# DMXW_Driver_Board.net
KiCad netlist of a schematic drawn in EAGLE
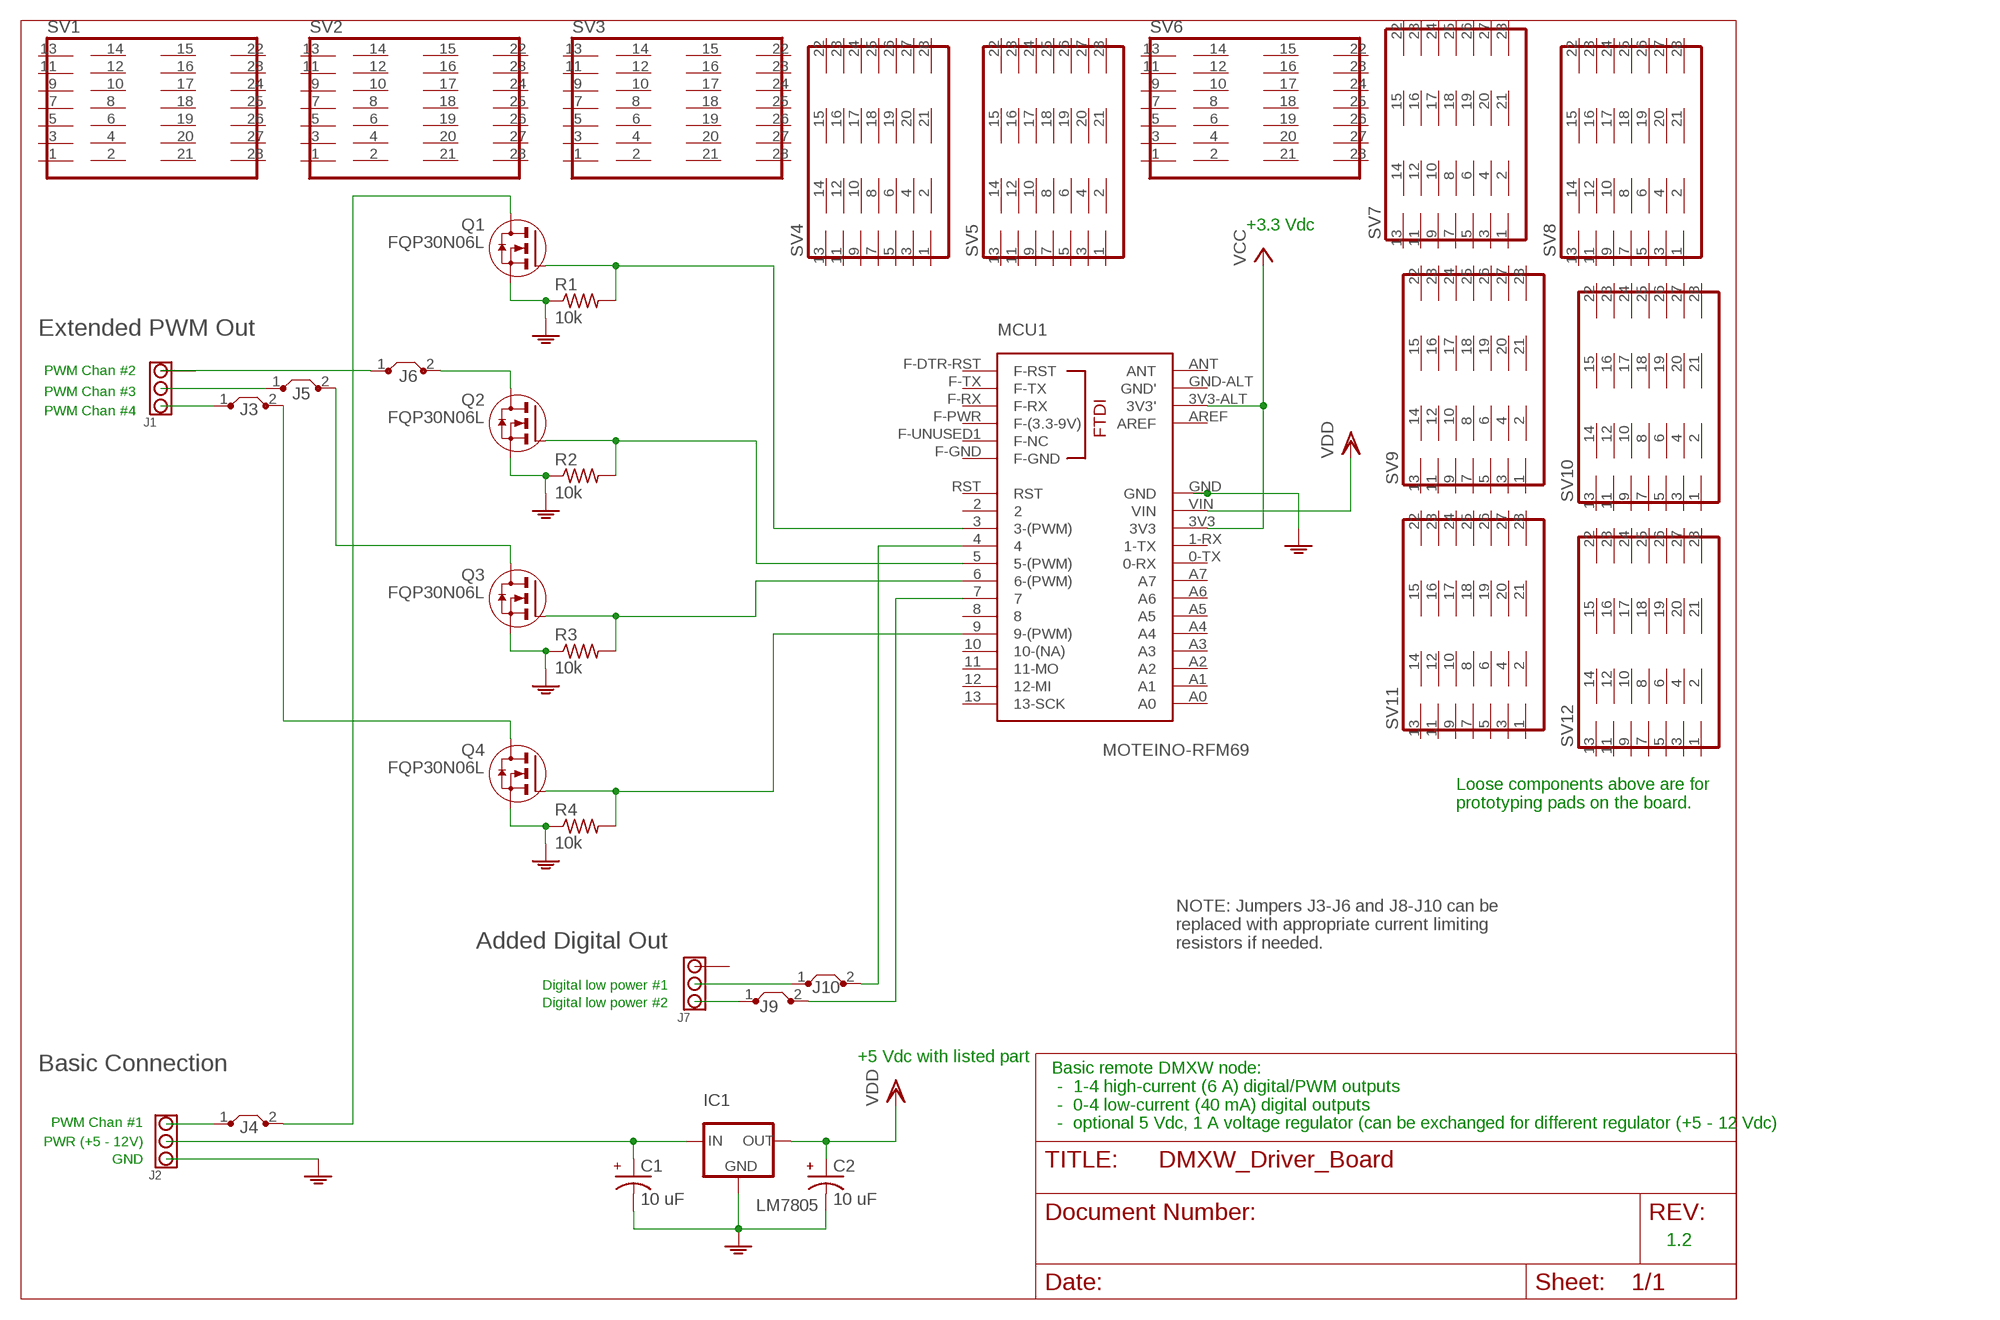
[diagram p0: schematic, sheet 1]

(export (version "E")
  (design (tool "Eeschema 10.0.6"))
  (components
    (comp (ref "C1")
      (value "10 uF")
      (footprint "eagle-import:RADIAL-CANISTER")
      (libsource (lib "eagle-import") (part "CAPACITOR-ELECTROLYTICRADIALCANISTER"))
    )
    (comp (ref "C2")
      (value "10 uF")
      (footprint "eagle-import:RADIAL-CANISTER")
      (libsource (lib "eagle-import") (part "CAPACITOR-ELECTROLYTICRADIALCANISTER"))
    )
    (comp (ref "IC1")
      (value "LM7805")
      (footprint "eagle-import:TO-220")
      (libsource (lib "eagle-import") (part "78XX-VOLTAGEREGULATORS"))
    )
    (comp (ref "J1")
      (value "TERMINAL-BLOCK-3")
      (footprint "eagle-import:W237-103")
      (libsource (lib "eagle-import") (part "TERMINAL-BLOCK-3"))
    )
    (comp (ref "J2")
      (value "TERMINAL-BLOCK-3")
      (footprint "eagle-import:W237-103")
      (libsource (lib "eagle-import") (part "TERMINAL-BLOCK-3"))
    )
    (comp (ref "J3")
      (value "J5MM")
      (footprint "eagle-import:05")
      (libsource (lib "eagle-import") (part "J5MM"))
    )
    (comp (ref "J4")
      (value "J5MM")
      (footprint "eagle-import:05")
      (libsource (lib "eagle-import") (part "J5MM"))
    )
    (comp (ref "J5")
      (value "J5MM")
      (footprint "eagle-import:05")
      (libsource (lib "eagle-import") (part "J5MM"))
    )
    (comp (ref "J6")
      (value "J5MM")
      (footprint "eagle-import:05")
      (libsource (lib "eagle-import") (part "J5MM"))
    )
    (comp (ref "J7")
      (value "TERMINAL-BLOCK-3")
      (footprint "eagle-import:W237-103")
      (libsource (lib "eagle-import") (part "TERMINAL-BLOCK-3"))
    )
    (comp (ref "J9")
      (value "J5MM")
      (footprint "eagle-import:05")
      (libsource (lib "eagle-import") (part "J5MM"))
    )
    (comp (ref "J10")
      (value "J5MM")
      (footprint "eagle-import:05")
      (libsource (lib "eagle-import") (part "J5MM"))
    )
    (comp (ref "MCU1")
      (value "MOTEINO-RFM69")
      (footprint "eagle-import:MOTEINO")
      (libsource (lib "eagle-import") (part "MOTEINO-RFM69"))
    )
    (comp (ref "Q1")
      (value "FQP30N06L")
      (footprint "eagle-import:TO-220")
      (libsource (lib "eagle-import") (part "MOSFET-N-FQP30N06L"))
    )
    (comp (ref "Q2")
      (value "FQP30N06L")
      (footprint "eagle-import:TO-220")
      (libsource (lib "eagle-import") (part "MOSFET-N-FQP30N06L"))
    )
    (comp (ref "Q3")
      (value "FQP30N06L")
      (footprint "eagle-import:TO-220")
      (libsource (lib "eagle-import") (part "MOSFET-N-FQP30N06L"))
    )
    (comp (ref "Q4")
      (value "FQP30N06L")
      (footprint "eagle-import:TO-220")
      (libsource (lib "eagle-import") (part "MOSFET-N-FQP30N06L"))
    )
    (comp (ref "R1")
      (value "10k")
      (footprint "eagle-import:0207_10")
      (libsource (lib "eagle-import") (part "R-US_0207/10"))
    )
    (comp (ref "R2")
      (value "10k")
      (footprint "eagle-import:0207_10")
      (libsource (lib "eagle-import") (part "R-US_0207/10"))
    )
    (comp (ref "R3")
      (value "10k")
      (footprint "eagle-import:0207_10")
      (libsource (lib "eagle-import") (part "R-US_0207/10"))
    )
    (comp (ref "R4")
      (value "10k")
      (footprint "eagle-import:0207_10")
      (libsource (lib "eagle-import") (part "R-US_0207/10"))
    )
    (comp (ref "SV1")
      (value "14P")
      (footprint "eagle-import:14P")
      (libsource (lib "eagle-import") (part "14P"))
    )
    (comp (ref "SV2")
      (value "14P")
      (footprint "eagle-import:14P")
      (libsource (lib "eagle-import") (part "14P"))
    )
    (comp (ref "SV3")
      (value "14P")
      (footprint "eagle-import:14P")
      (libsource (lib "eagle-import") (part "14P"))
    )
    (comp (ref "SV4")
      (value "14P")
      (footprint "eagle-import:14P")
      (libsource (lib "eagle-import") (part "14P"))
    )
    (comp (ref "SV5")
      (value "14P")
      (footprint "eagle-import:14P")
      (libsource (lib "eagle-import") (part "14P"))
    )
    (comp (ref "SV6")
      (value "14P")
      (footprint "eagle-import:14P")
      (libsource (lib "eagle-import") (part "14P"))
    )
    (comp (ref "SV7")
      (value "14P")
      (footprint "eagle-import:14P")
      (libsource (lib "eagle-import") (part "14P"))
    )
    (comp (ref "SV8")
      (value "14P")
      (footprint "eagle-import:14P")
      (libsource (lib "eagle-import") (part "14P"))
    )
    (comp (ref "SV9")
      (value "14P")
      (footprint "eagle-import:14P")
      (libsource (lib "eagle-import") (part "14P"))
    )
    (comp (ref "SV10")
      (value "14P")
      (footprint "eagle-import:14P")
      (libsource (lib "eagle-import") (part "14P"))
    )
    (comp (ref "SV11")
      (value "14P")
      (footprint "eagle-import:14P")
      (libsource (lib "eagle-import") (part "14P"))
    )
    (comp (ref "SV12")
      (value "14P")
      (footprint "eagle-import:14P")
      (libsource (lib "eagle-import") (part "14P"))
    )
  )
  (nets
    (net (code "1") (name "GND") (class "Default")
      (node (ref "C1") (pin "-") (pinfunction "-_-") (pintype "passive"))
      (node (ref "C2") (pin "-") (pinfunction "-_-") (pintype "passive"))
      (node (ref "IC1") (pin "PIN2") (pinfunction "GND_PIN2") (pintype "input"))
      (node (ref "J2") (pin "3") (pinfunction "P$3_3") (pintype "bidirectional"))
      (node (ref "MCU1") (pin "GND") (pinfunction "GND_GND") (pintype "bidirectional"))
      (node (ref "Q1") (pin "PIN3") (pinfunction "S_PIN3") (pintype "passive"))
      (node (ref "Q2") (pin "PIN3") (pinfunction "S_PIN3") (pintype "passive"))
      (node (ref "Q3") (pin "PIN3") (pinfunction "S_PIN3") (pintype "passive"))
      (node (ref "Q4") (pin "PIN3") (pinfunction "S_PIN3") (pintype "passive"))
      (node (ref "R1") (pin "1") (pinfunction "1_1") (pintype "passive"))
      (node (ref "R2") (pin "1") (pinfunction "1_1") (pintype "passive"))
      (node (ref "R3") (pin "1") (pinfunction "1_1") (pintype "passive"))
      (node (ref "R4") (pin "1") (pinfunction "1_1") (pintype "passive"))
    )
    (net (code "2") (name "Net-(IC1-IN)") (class "Default")
      (node (ref "C1") (pin "+") (pinfunction "+_+") (pintype "passive"))
      (node (ref "IC1") (pin "PIN1") (pinfunction "IN_PIN1") (pintype "input"))
      (node (ref "J2") (pin "2") (pinfunction "P$2_2") (pintype "bidirectional"))
    )
    (net (code "3") (name "Net-(J1-P$1)") (class "Default")
      (node (ref "J1") (pin "1") (pinfunction "P$1_1") (pintype "bidirectional"))
      (node (ref "J6") (pin "1") (pinfunction "1_1") (pintype "passive"))
    )
    (net (code "4") (name "Net-(J1-P$2)") (class "Default")
      (node (ref "J1") (pin "2") (pinfunction "P$2_2") (pintype "bidirectional"))
      (node (ref "J5") (pin "1") (pinfunction "1_1") (pintype "passive"))
    )
    (net (code "5") (name "Net-(J1-P$3)") (class "Default")
      (node (ref "J1") (pin "3") (pinfunction "P$3_3") (pintype "bidirectional"))
      (node (ref "J3") (pin "1") (pinfunction "1_1") (pintype "passive"))
    )
    (net (code "6") (name "Net-(J2-P$1)") (class "Default")
      (node (ref "J2") (pin "1") (pinfunction "P$1_1") (pintype "bidirectional"))
      (node (ref "J4") (pin "1") (pinfunction "1_1") (pintype "passive"))
    )
    (net (code "7") (name "Net-(J7-P$2)") (class "Default")
      (node (ref "J10") (pin "1") (pinfunction "1_1") (pintype "passive"))
      (node (ref "J7") (pin "2") (pinfunction "P$2_2") (pintype "bidirectional"))
    )
    (net (code "8") (name "Net-(J7-P$3)") (class "Default")
      (node (ref "J7") (pin "3") (pinfunction "P$3_3") (pintype "bidirectional"))
      (node (ref "J9") (pin "1") (pinfunction "1_1") (pintype "passive"))
    )
    (net (code "9") (name "Net-(J9-Pad2)") (class "Default")
      (node (ref "J9") (pin "2") (pinfunction "2_2") (pintype "passive"))
      (node (ref "MCU1") (pin "7") (pinfunction "7_7") (pintype "bidirectional"))
    )
    (net (code "10") (name "Net-(J10-Pad2)") (class "Default")
      (node (ref "J10") (pin "2") (pinfunction "2_2") (pintype "passive"))
      (node (ref "MCU1") (pin "4") (pinfunction "4_4") (pintype "bidirectional"))
    )
    (net (code "11") (name "Net-(MCU1-3-(PWM))") (class "Default")
      (node (ref "MCU1") (pin "3") (pinfunction "3-(PWM)_3") (pintype "bidirectional"))
      (node (ref "Q1") (pin "PIN1") (pinfunction "G_PIN1") (pintype "passive"))
      (node (ref "R1") (pin "2") (pinfunction "2_2") (pintype "passive"))
    )
    (net (code "12") (name "Net-(MCU1-5-(PWM))") (class "Default")
      (node (ref "MCU1") (pin "5") (pinfunction "5-(PWM)_5") (pintype "bidirectional"))
      (node (ref "Q2") (pin "PIN1") (pinfunction "G_PIN1") (pintype "passive"))
      (node (ref "R2") (pin "2") (pinfunction "2_2") (pintype "passive"))
    )
    (net (code "13") (name "Net-(MCU1-6-(PWM))") (class "Default")
      (node (ref "MCU1") (pin "6") (pinfunction "6-(PWM)_6") (pintype "bidirectional"))
      (node (ref "Q3") (pin "PIN1") (pinfunction "G_PIN1") (pintype "passive"))
      (node (ref "R3") (pin "2") (pinfunction "2_2") (pintype "passive"))
    )
    (net (code "14") (name "Net-(MCU1-9-(PWM))") (class "Default")
      (node (ref "MCU1") (pin "9") (pinfunction "9-(PWM)_9") (pintype "bidirectional"))
      (node (ref "Q4") (pin "PIN1") (pinfunction "G_PIN1") (pintype "passive"))
      (node (ref "R4") (pin "2") (pinfunction "2_2") (pintype "passive"))
    )
    (net (code "15") (name "Net-(Q1-D)") (class "Default")
      (node (ref "J4") (pin "2") (pinfunction "2_2") (pintype "passive"))
      (node (ref "Q1") (pin "PIN2") (pinfunction "D_PIN2") (pintype "passive"))
    )
    (net (code "16") (name "Net-(Q2-D)") (class "Default")
      (node (ref "J6") (pin "2") (pinfunction "2_2") (pintype "passive"))
      (node (ref "Q2") (pin "PIN2") (pinfunction "D_PIN2") (pintype "passive"))
    )
    (net (code "17") (name "Net-(Q3-D)") (class "Default")
      (node (ref "J5") (pin "2") (pinfunction "2_2") (pintype "passive"))
      (node (ref "Q3") (pin "PIN2") (pinfunction "D_PIN2") (pintype "passive"))
    )
    (net (code "18") (name "Net-(Q4-D)") (class "Default")
      (node (ref "J3") (pin "2") (pinfunction "2_2") (pintype "passive"))
      (node (ref "Q4") (pin "PIN2") (pinfunction "D_PIN2") (pintype "passive"))
    )
    (net (code "19") (name "VCC") (class "Default")
      (node (ref "MCU1") (pin "3V3") (pinfunction "3V3_3V3") (pintype "bidirectional"))
      (node (ref "MCU1") (pin "3V3-ALT") (pinfunction "3V3'_3V3-ALT") (pintype "bidirectional"))
    )
    (net (code "20") (name "VDD") (class "Default")
      (node (ref "C2") (pin "+") (pinfunction "+_+") (pintype "passive"))
      (node (ref "IC1") (pin "PIN3") (pinfunction "OUT_PIN3") (pintype "passive"))
      (node (ref "MCU1") (pin "VIN") (pinfunction "VIN_VIN") (pintype "bidirectional"))
    )
    (net (code "21") (name "unconnected-(J7-P$1-Pad1)") (class "Default")
      (node (ref "J7") (pin "1") (pinfunction "P$1_1") (pintype "bidirectional"))
    )
    (net (code "22") (name "unconnected-(MCU1-0-RX-Pad0-TX)") (class "Default")
      (node (ref "MCU1") (pin "0-TX") (pinfunction "0-RX_0-TX") (pintype "bidirectional"))
    )
    (net (code "23") (name "unconnected-(MCU1-1-TX-Pad1-RX)") (class "Default")
      (node (ref "MCU1") (pin "1-RX") (pinfunction "1-TX_1-RX") (pintype "bidirectional"))
    )
    (net (code "24") (name "unconnected-(MCU1-10-(NA)-Pad10)") (class "Default")
      (node (ref "MCU1") (pin "10") (pinfunction "10-(NA)_10") (pintype "bidirectional"))
    )
    (net (code "25") (name "unconnected-(MCU1-11-MO-Pad11)") (class "Default")
      (node (ref "MCU1") (pin "11") (pinfunction "11-MO_11") (pintype "bidirectional"))
    )
    (net (code "26") (name "unconnected-(MCU1-12-MI-Pad12)") (class "Default")
      (node (ref "MCU1") (pin "12") (pinfunction "12-MI_12") (pintype "bidirectional"))
    )
    (net (code "27") (name "unconnected-(MCU1-13-SCK-Pad13)") (class "Default")
      (node (ref "MCU1") (pin "13") (pinfunction "13-SCK_13") (pintype "bidirectional"))
    )
    (net (code "28") (name "unconnected-(MCU1-F-(3.3-9V)-PadF-PWR)") (class "Default")
      (node (ref "MCU1") (pin "F-PWR") (pinfunction "F-(3.3-9V)_F-PWR") (pintype "bidirectional"))
    )
    (net (code "29") (name "unconnected-(MCU1-F-NC-PadF-UNUSED1)") (class "Default")
      (node (ref "MCU1") (pin "F-UNUSED1") (pinfunction "F-NC_F-UNUSED1") (pintype "bidirectional"))
    )
    (net (code "30") (name "unconnected-(MCU1-F-RST-PadF-DTR-RST)") (class "Default")
      (node (ref "MCU1") (pin "F-DTR-RST") (pinfunction "F-RST_F-DTR-RST") (pintype "bidirectional"))
    )
    (net (code "31") (name "unconnected-(MCU1-GND'-PadGND-ALT)") (class "Default")
      (node (ref "MCU1") (pin "GND-ALT") (pinfunction "GND'_GND-ALT") (pintype "bidirectional"))
    )
    (net (code "32") (name "unconnected-(MCU1-Pad2)") (class "Default")
      (node (ref "MCU1") (pin "2") (pinfunction "2_2") (pintype "bidirectional"))
    )
    (net (code "33") (name "unconnected-(MCU1-Pad8)") (class "Default")
      (node (ref "MCU1") (pin "8") (pinfunction "8_8") (pintype "bidirectional"))
    )
    (net (code "34") (name "unconnected-(MCU1-PadA0)") (class "Default")
      (node (ref "MCU1") (pin "A0") (pinfunction "A0_A0") (pintype "bidirectional"))
    )
    (net (code "35") (name "unconnected-(MCU1-PadA1)") (class "Default")
      (node (ref "MCU1") (pin "A1") (pinfunction "A1_A1") (pintype "bidirectional"))
    )
    (net (code "36") (name "unconnected-(MCU1-PadA2)") (class "Default")
      (node (ref "MCU1") (pin "A2") (pinfunction "A2_A2") (pintype "bidirectional"))
    )
    (net (code "37") (name "unconnected-(MCU1-PadA3)") (class "Default")
      (node (ref "MCU1") (pin "A3") (pinfunction "A3_A3") (pintype "bidirectional"))
    )
    (net (code "38") (name "unconnected-(MCU1-PadA4)") (class "Default")
      (node (ref "MCU1") (pin "A4") (pinfunction "A4_A4") (pintype "bidirectional"))
    )
    (net (code "39") (name "unconnected-(MCU1-PadA5)") (class "Default")
      (node (ref "MCU1") (pin "A5") (pinfunction "A5_A5") (pintype "bidirectional"))
    )
    (net (code "40") (name "unconnected-(MCU1-PadA6)") (class "Default")
      (node (ref "MCU1") (pin "A6") (pinfunction "A6_A6") (pintype "bidirectional"))
    )
    (net (code "41") (name "unconnected-(MCU1-PadA7)") (class "Default")
      (node (ref "MCU1") (pin "A7") (pinfunction "A7_A7") (pintype "bidirectional"))
    )
    (net (code "42") (name "unconnected-(MCU1-PadANT)") (class "Default")
      (node (ref "MCU1") (pin "ANT") (pinfunction "ANT_ANT") (pintype "bidirectional"))
    )
    (net (code "43") (name "unconnected-(MCU1-PadAREF)") (class "Default")
      (node (ref "MCU1") (pin "AREF") (pinfunction "AREF_AREF") (pintype "bidirectional"))
    )
    (net (code "44") (name "unconnected-(MCU1-PadF-GND)") (class "Default")
      (node (ref "MCU1") (pin "F-GND") (pinfunction "F-GND_F-GND") (pintype "bidirectional"))
    )
    (net (code "45") (name "unconnected-(MCU1-PadF-RX)") (class "Default")
      (node (ref "MCU1") (pin "F-RX") (pinfunction "F-RX_F-RX") (pintype "bidirectional"))
    )
    (net (code "46") (name "unconnected-(MCU1-PadF-TX)") (class "Default")
      (node (ref "MCU1") (pin "F-TX") (pinfunction "F-TX_F-TX") (pintype "bidirectional"))
    )
    (net (code "47") (name "unconnected-(MCU1-PadRST)") (class "Default")
      (node (ref "MCU1") (pin "RST") (pinfunction "RST_RST") (pintype "bidirectional"))
    )
    (net (code "48") (name "unconnected-(SV1-Pad1)") (class "Default")
      (node (ref "SV1") (pin "1") (pinfunction "1_1") (pintype "passive"))
    )
    (net (code "49") (name "unconnected-(SV1-Pad2)") (class "Default")
      (node (ref "SV1") (pin "2") (pinfunction "2_2") (pintype "passive"))
    )
    (net (code "50") (name "unconnected-(SV1-Pad3)") (class "Default")
      (node (ref "SV1") (pin "3") (pinfunction "3_3") (pintype "passive"))
    )
    (net (code "51") (name "unconnected-(SV1-Pad4)") (class "Default")
      (node (ref "SV1") (pin "4") (pinfunction "4_4") (pintype "passive"))
    )
    (net (code "52") (name "unconnected-(SV1-Pad5)") (class "Default")
      (node (ref "SV1") (pin "5") (pinfunction "5_5") (pintype "passive"))
    )
    (net (code "53") (name "unconnected-(SV1-Pad6)") (class "Default")
      (node (ref "SV1") (pin "6") (pinfunction "6_6") (pintype "passive"))
    )
    (net (code "54") (name "unconnected-(SV1-Pad7)") (class "Default")
      (node (ref "SV1") (pin "7") (pinfunction "7_7") (pintype "passive"))
    )
    (net (code "55") (name "unconnected-(SV1-Pad8)") (class "Default")
      (node (ref "SV1") (pin "8") (pinfunction "8_8") (pintype "passive"))
    )
    (net (code "56") (name "unconnected-(SV1-Pad9)") (class "Default")
      (node (ref "SV1") (pin "9") (pinfunction "9_9") (pintype "passive"))
    )
    (net (code "57") (name "unconnected-(SV1-Pad10)") (class "Default")
      (node (ref "SV1") (pin "10") (pinfunction "10_10") (pintype "passive"))
    )
    (net (code "58") (name "unconnected-(SV1-Pad11)") (class "Default")
      (node (ref "SV1") (pin "11") (pinfunction "11_11") (pintype "passive"))
    )
    (net (code "59") (name "unconnected-(SV1-Pad12)") (class "Default")
      (node (ref "SV1") (pin "12") (pinfunction "12_12") (pintype "passive"))
    )
    (net (code "60") (name "unconnected-(SV1-Pad13)") (class "Default")
      (node (ref "SV1") (pin "13") (pinfunction "13_13") (pintype "passive"))
    )
    (net (code "61") (name "unconnected-(SV1-Pad14)") (class "Default")
      (node (ref "SV1") (pin "14") (pinfunction "14_14") (pintype "passive"))
    )
    (net (code "62") (name "unconnected-(SV1-Pad15)") (class "Default")
      (node (ref "SV1") (pin "15") (pinfunction "15_15") (pintype "passive"))
    )
    (net (code "63") (name "unconnected-(SV1-Pad16)") (class "Default")
      (node (ref "SV1") (pin "16") (pinfunction "16_16") (pintype "passive"))
    )
    (net (code "64") (name "unconnected-(SV1-Pad17)") (class "Default")
      (node (ref "SV1") (pin "17") (pinfunction "17_17") (pintype "passive"))
    )
    (net (code "65") (name "unconnected-(SV1-Pad18)") (class "Default")
      (node (ref "SV1") (pin "18") (pinfunction "18_18") (pintype "passive"))
    )
    (net (code "66") (name "unconnected-(SV1-Pad19)") (class "Default")
      (node (ref "SV1") (pin "19") (pinfunction "19_19") (pintype "passive"))
    )
    (net (code "67") (name "unconnected-(SV1-Pad20)") (class "Default")
      (node (ref "SV1") (pin "20") (pinfunction "20_20") (pintype "passive"))
    )
    (net (code "68") (name "unconnected-(SV1-Pad21)") (class "Default")
      (node (ref "SV1") (pin "21") (pinfunction "21_21") (pintype "passive"))
    )
    (net (code "69") (name "unconnected-(SV1-Pad22)") (class "Default")
      (node (ref "SV1") (pin "22") (pinfunction "22_22") (pintype "passive"))
    )
    (net (code "70") (name "unconnected-(SV1-Pad23)") (class "Default")
      (node (ref "SV1") (pin "23") (pinfunction "23_23") (pintype "passive"))
    )
    (net (code "71") (name "unconnected-(SV1-Pad24)") (class "Default")
      (node (ref "SV1") (pin "24") (pinfunction "24_24") (pintype "passive"))
    )
    (net (code "72") (name "unconnected-(SV1-Pad25)") (class "Default")
      (node (ref "SV1") (pin "25") (pinfunction "25_25") (pintype "passive"))
    )
    (net (code "73") (name "unconnected-(SV1-Pad26)") (class "Default")
      (node (ref "SV1") (pin "26") (pinfunction "26_26") (pintype "passive"))
    )
    (net (code "74") (name "unconnected-(SV1-Pad27)") (class "Default")
      (node (ref "SV1") (pin "27") (pinfunction "27_27") (pintype "passive"))
    )
    (net (code "75") (name "unconnected-(SV1-Pad28)") (class "Default")
      (node (ref "SV1") (pin "28") (pinfunction "28_28") (pintype "passive"))
    )
    (net (code "76") (name "unconnected-(SV2-Pad1)") (class "Default")
      (node (ref "SV2") (pin "1") (pinfunction "1_1") (pintype "passive"))
    )
    (net (code "77") (name "unconnected-(SV2-Pad2)") (class "Default")
      (node (ref "SV2") (pin "2") (pinfunction "2_2") (pintype "passive"))
    )
    (net (code "78") (name "unconnected-(SV2-Pad3)") (class "Default")
      (node (ref "SV2") (pin "3") (pinfunction "3_3") (pintype "passive"))
    )
    (net (code "79") (name "unconnected-(SV2-Pad4)") (class "Default")
      (node (ref "SV2") (pin "4") (pinfunction "4_4") (pintype "passive"))
    )
    (net (code "80") (name "unconnected-(SV2-Pad5)") (class "Default")
      (node (ref "SV2") (pin "5") (pinfunction "5_5") (pintype "passive"))
    )
    (net (code "81") (name "unconnected-(SV2-Pad6)") (class "Default")
      (node (ref "SV2") (pin "6") (pinfunction "6_6") (pintype "passive"))
    )
    (net (code "82") (name "unconnected-(SV2-Pad7)") (class "Default")
      (node (ref "SV2") (pin "7") (pinfunction "7_7") (pintype "passive"))
    )
    (net (code "83") (name "unconnected-(SV2-Pad8)") (class "Default")
      (node (ref "SV2") (pin "8") (pinfunction "8_8") (pintype "passive"))
    )
    (net (code "84") (name "unconnected-(SV2-Pad9)") (class "Default")
      (node (ref "SV2") (pin "9") (pinfunction "9_9") (pintype "passive"))
    )
    (net (code "85") (name "unconnected-(SV2-Pad10)") (class "Default")
      (node (ref "SV2") (pin "10") (pinfunction "10_10") (pintype "passive"))
    )
    (net (code "86") (name "unconnected-(SV2-Pad11)") (class "Default")
      (node (ref "SV2") (pin "11") (pinfunction "11_11") (pintype "passive"))
    )
    (net (code "87") (name "unconnected-(SV2-Pad12)") (class "Default")
      (node (ref "SV2") (pin "12") (pinfunction "12_12") (pintype "passive"))
    )
    (net (code "88") (name "unconnected-(SV2-Pad13)") (class "Default")
      (node (ref "SV2") (pin "13") (pinfunction "13_13") (pintype "passive"))
    )
    (net (code "89") (name "unconnected-(SV2-Pad14)") (class "Default")
      (node (ref "SV2") (pin "14") (pinfunction "14_14") (pintype "passive"))
    )
    (net (code "90") (name "unconnected-(SV2-Pad15)") (class "Default")
      (node (ref "SV2") (pin "15") (pinfunction "15_15") (pintype "passive"))
    )
    (net (code "91") (name "unconnected-(SV2-Pad16)") (class "Default")
      (node (ref "SV2") (pin "16") (pinfunction "16_16") (pintype "passive"))
    )
    (net (code "92") (name "unconnected-(SV2-Pad17)") (class "Default")
      (node (ref "SV2") (pin "17") (pinfunction "17_17") (pintype "passive"))
    )
    (net (code "93") (name "unconnected-(SV2-Pad18)") (class "Default")
      (node (ref "SV2") (pin "18") (pinfunction "18_18") (pintype "passive"))
    )
    (net (code "94") (name "unconnected-(SV2-Pad19)") (class "Default")
      (node (ref "SV2") (pin "19") (pinfunction "19_19") (pintype "passive"))
    )
    (net (code "95") (name "unconnected-(SV2-Pad20)") (class "Default")
      (node (ref "SV2") (pin "20") (pinfunction "20_20") (pintype "passive"))
    )
    (net (code "96") (name "unconnected-(SV2-Pad21)") (class "Default")
      (node (ref "SV2") (pin "21") (pinfunction "21_21") (pintype "passive"))
    )
    (net (code "97") (name "unconnected-(SV2-Pad22)") (class "Default")
      (node (ref "SV2") (pin "22") (pinfunction "22_22") (pintype "passive"))
    )
    (net (code "98") (name "unconnected-(SV2-Pad23)") (class "Default")
      (node (ref "SV2") (pin "23") (pinfunction "23_23") (pintype "passive"))
    )
    (net (code "99") (name "unconnected-(SV2-Pad24)") (class "Default")
      (node (ref "SV2") (pin "24") (pinfunction "24_24") (pintype "passive"))
    )
    (net (code "100") (name "unconnected-(SV2-Pad25)") (class "Default")
      (node (ref "SV2") (pin "25") (pinfunction "25_25") (pintype "passive"))
    )
    (net (code "101") (name "unconnected-(SV2-Pad26)") (class "Default")
      (node (ref "SV2") (pin "26") (pinfunction "26_26") (pintype "passive"))
    )
    (net (code "102") (name "unconnected-(SV2-Pad27)") (class "Default")
      (node (ref "SV2") (pin "27") (pinfunction "27_27") (pintype "passive"))
    )
    (net (code "103") (name "unconnected-(SV2-Pad28)") (class "Default")
      (node (ref "SV2") (pin "28") (pinfunction "28_28") (pintype "passive"))
    )
    (net (code "104") (name "unconnected-(SV3-Pad1)") (class "Default")
      (node (ref "SV3") (pin "1") (pinfunction "1_1") (pintype "passive"))
    )
    (net (code "105") (name "unconnected-(SV3-Pad2)") (class "Default")
      (node (ref "SV3") (pin "2") (pinfunction "2_2") (pintype "passive"))
    )
    (net (code "106") (name "unconnected-(SV3-Pad3)") (class "Default")
      (node (ref "SV3") (pin "3") (pinfunction "3_3") (pintype "passive"))
    )
    (net (code "107") (name "unconnected-(SV3-Pad4)") (class "Default")
      (node (ref "SV3") (pin "4") (pinfunction "4_4") (pintype "passive"))
    )
    (net (code "108") (name "unconnected-(SV3-Pad5)") (class "Default")
      (node (ref "SV3") (pin "5") (pinfunction "5_5") (pintype "passive"))
    )
    (net (code "109") (name "unconnected-(SV3-Pad6)") (class "Default")
      (node (ref "SV3") (pin "6") (pinfunction "6_6") (pintype "passive"))
    )
    (net (code "110") (name "unconnected-(SV3-Pad7)") (class "Default")
      (node (ref "SV3") (pin "7") (pinfunction "7_7") (pintype "passive"))
    )
    (net (code "111") (name "unconnected-(SV3-Pad8)") (class "Default")
      (node (ref "SV3") (pin "8") (pinfunction "8_8") (pintype "passive"))
    )
    (net (code "112") (name "unconnected-(SV3-Pad9)") (class "Default")
      (node (ref "SV3") (pin "9") (pinfunction "9_9") (pintype "passive"))
    )
    (net (code "113") (name "unconnected-(SV3-Pad10)") (class "Default")
      (node (ref "SV3") (pin "10") (pinfunction "10_10") (pintype "passive"))
    )
    (net (code "114") (name "unconnected-(SV3-Pad11)") (class "Default")
      (node (ref "SV3") (pin "11") (pinfunction "11_11") (pintype "passive"))
    )
    (net (code "115") (name "unconnected-(SV3-Pad12)") (class "Default")
      (node (ref "SV3") (pin "12") (pinfunction "12_12") (pintype "passive"))
    )
    (net (code "116") (name "unconnected-(SV3-Pad13)") (class "Default")
      (node (ref "SV3") (pin "13") (pinfunction "13_13") (pintype "passive"))
    )
    (net (code "117") (name "unconnected-(SV3-Pad14)") (class "Default")
      (node (ref "SV3") (pin "14") (pinfunction "14_14") (pintype "passive"))
    )
    (net (code "118") (name "unconnected-(SV3-Pad15)") (class "Default")
      (node (ref "SV3") (pin "15") (pinfunction "15_15") (pintype "passive"))
    )
    (net (code "119") (name "unconnected-(SV3-Pad16)") (class "Default")
      (node (ref "SV3") (pin "16") (pinfunction "16_16") (pintype "passive"))
    )
    (net (code "120") (name "unconnected-(SV3-Pad17)") (class "Default")
      (node (ref "SV3") (pin "17") (pinfunction "17_17") (pintype "passive"))
    )
    (net (code "121") (name "unconnected-(SV3-Pad18)") (class "Default")
      (node (ref "SV3") (pin "18") (pinfunction "18_18") (pintype "passive"))
    )
    (net (code "122") (name "unconnected-(SV3-Pad19)") (class "Default")
      (node (ref "SV3") (pin "19") (pinfunction "19_19") (pintype "passive"))
    )
    (net (code "123") (name "unconnected-(SV3-Pad20)") (class "Default")
      (node (ref "SV3") (pin "20") (pinfunction "20_20") (pintype "passive"))
    )
    (net (code "124") (name "unconnected-(SV3-Pad21)") (class "Default")
      (node (ref "SV3") (pin "21") (pinfunction "21_21") (pintype "passive"))
    )
    (net (code "125") (name "unconnected-(SV3-Pad22)") (class "Default")
      (node (ref "SV3") (pin "22") (pinfunction "22_22") (pintype "passive"))
    )
    (net (code "126") (name "unconnected-(SV3-Pad23)") (class "Default")
      (node (ref "SV3") (pin "23") (pinfunction "23_23") (pintype "passive"))
    )
    (net (code "127") (name "unconnected-(SV3-Pad24)") (class "Default")
      (node (ref "SV3") (pin "24") (pinfunction "24_24") (pintype "passive"))
    )
    (net (code "128") (name "unconnected-(SV3-Pad25)") (class "Default")
      (node (ref "SV3") (pin "25") (pinfunction "25_25") (pintype "passive"))
    )
    (net (code "129") (name "unconnected-(SV3-Pad26)") (class "Default")
      (node (ref "SV3") (pin "26") (pinfunction "26_26") (pintype "passive"))
    )
    (net (code "130") (name "unconnected-(SV3-Pad27)") (class "Default")
      (node (ref "SV3") (pin "27") (pinfunction "27_27") (pintype "passive"))
    )
    (net (code "131") (name "unconnected-(SV3-Pad28)") (class "Default")
      (node (ref "SV3") (pin "28") (pinfunction "28_28") (pintype "passive"))
    )
    (net (code "132") (name "unconnected-(SV4-Pad1)") (class "Default")
      (node (ref "SV4") (pin "1") (pinfunction "1_1") (pintype "passive"))
    )
    (net (code "133") (name "unconnected-(SV4-Pad2)") (class "Default")
      (node (ref "SV4") (pin "2") (pinfunction "2_2") (pintype "passive"))
    )
    (net (code "134") (name "unconnected-(SV4-Pad3)") (class "Default")
      (node (ref "SV4") (pin "3") (pinfunction "3_3") (pintype "passive"))
    )
    (net (code "135") (name "unconnected-(SV4-Pad4)") (class "Default")
      (node (ref "SV4") (pin "4") (pinfunction "4_4") (pintype "passive"))
    )
    (net (code "136") (name "unconnected-(SV4-Pad5)") (class "Default")
      (node (ref "SV4") (pin "5") (pinfunction "5_5") (pintype "passive"))
    )
    (net (code "137") (name "unconnected-(SV4-Pad6)") (class "Default")
      (node (ref "SV4") (pin "6") (pinfunction "6_6") (pintype "passive"))
    )
    (net (code "138") (name "unconnected-(SV4-Pad7)") (class "Default")
      (node (ref "SV4") (pin "7") (pinfunction "7_7") (pintype "passive"))
    )
    (net (code "139") (name "unconnected-(SV4-Pad8)") (class "Default")
      (node (ref "SV4") (pin "8") (pinfunction "8_8") (pintype "passive"))
    )
    (net (code "140") (name "unconnected-(SV4-Pad9)") (class "Default")
      (node (ref "SV4") (pin "9") (pinfunction "9_9") (pintype "passive"))
    )
    (net (code "141") (name "unconnected-(SV4-Pad10)") (class "Default")
      (node (ref "SV4") (pin "10") (pinfunction "10_10") (pintype "passive"))
    )
    (net (code "142") (name "unconnected-(SV4-Pad11)") (class "Default")
      (node (ref "SV4") (pin "11") (pinfunction "11_11") (pintype "passive"))
    )
    (net (code "143") (name "unconnected-(SV4-Pad12)") (class "Default")
      (node (ref "SV4") (pin "12") (pinfunction "12_12") (pintype "passive"))
    )
    (net (code "144") (name "unconnected-(SV4-Pad13)") (class "Default")
      (node (ref "SV4") (pin "13") (pinfunction "13_13") (pintype "passive"))
    )
    (net (code "145") (name "unconnected-(SV4-Pad14)") (class "Default")
      (node (ref "SV4") (pin "14") (pinfunction "14_14") (pintype "passive"))
    )
    (net (code "146") (name "unconnected-(SV4-Pad15)") (class "Default")
      (node (ref "SV4") (pin "15") (pinfunction "15_15") (pintype "passive"))
    )
    (net (code "147") (name "unconnected-(SV4-Pad16)") (class "Default")
      (node (ref "SV4") (pin "16") (pinfunction "16_16") (pintype "passive"))
    )
    (net (code "148") (name "unconnected-(SV4-Pad17)") (class "Default")
      (node (ref "SV4") (pin "17") (pinfunction "17_17") (pintype "passive"))
    )
    (net (code "149") (name "unconnected-(SV4-Pad18)") (class "Default")
      (node (ref "SV4") (pin "18") (pinfunction "18_18") (pintype "passive"))
    )
    (net (code "150") (name "unconnected-(SV4-Pad19)") (class "Default")
      (node (ref "SV4") (pin "19") (pinfunction "19_19") (pintype "passive"))
    )
    (net (code "151") (name "unconnected-(SV4-Pad20)") (class "Default")
      (node (ref "SV4") (pin "20") (pinfunction "20_20") (pintype "passive"))
    )
    (net (code "152") (name "unconnected-(SV4-Pad21)") (class "Default")
      (node (ref "SV4") (pin "21") (pinfunction "21_21") (pintype "passive"))
    )
    (net (code "153") (name "unconnected-(SV4-Pad22)") (class "Default")
      (node (ref "SV4") (pin "22") (pinfunction "22_22") (pintype "passive"))
    )
    (net (code "154") (name "unconnected-(SV4-Pad23)") (class "Default")
      (node (ref "SV4") (pin "23") (pinfunction "23_23") (pintype "passive"))
    )
    (net (code "155") (name "unconnected-(SV4-Pad24)") (class "Default")
      (node (ref "SV4") (pin "24") (pinfunction "24_24") (pintype "passive"))
    )
    (net (code "156") (name "unconnected-(SV4-Pad25)") (class "Default")
      (node (ref "SV4") (pin "25") (pinfunction "25_25") (pintype "passive"))
    )
    (net (code "157") (name "unconnected-(SV4-Pad26)") (class "Default")
      (node (ref "SV4") (pin "26") (pinfunction "26_26") (pintype "passive"))
    )
    (net (code "158") (name "unconnected-(SV4-Pad27)") (class "Default")
      (node (ref "SV4") (pin "27") (pinfunction "27_27") (pintype "passive"))
    )
    (net (code "159") (name "unconnected-(SV4-Pad28)") (class "Default")
      (node (ref "SV4") (pin "28") (pinfunction "28_28") (pintype "passive"))
    )
    (net (code "160") (name "unconnected-(SV5-Pad1)") (class "Default")
      (node (ref "SV5") (pin "1") (pinfunction "1_1") (pintype "passive"))
    )
    (net (code "161") (name "unconnected-(SV5-Pad2)") (class "Default")
      (node (ref "SV5") (pin "2") (pinfunction "2_2") (pintype "passive"))
    )
    (net (code "162") (name "unconnected-(SV5-Pad3)") (class "Default")
      (node (ref "SV5") (pin "3") (pinfunction "3_3") (pintype "passive"))
    )
    (net (code "163") (name "unconnected-(SV5-Pad4)") (class "Default")
      (node (ref "SV5") (pin "4") (pinfunction "4_4") (pintype "passive"))
    )
    (net (code "164") (name "unconnected-(SV5-Pad5)") (class "Default")
      (node (ref "SV5") (pin "5") (pinfunction "5_5") (pintype "passive"))
    )
    (net (code "165") (name "unconnected-(SV5-Pad6)") (class "Default")
      (node (ref "SV5") (pin "6") (pinfunction "6_6") (pintype "passive"))
    )
    (net (code "166") (name "unconnected-(SV5-Pad7)") (class "Default")
      (node (ref "SV5") (pin "7") (pinfunction "7_7") (pintype "passive"))
    )
    (net (code "167") (name "unconnected-(SV5-Pad8)") (class "Default")
      (node (ref "SV5") (pin "8") (pinfunction "8_8") (pintype "passive"))
    )
    (net (code "168") (name "unconnected-(SV5-Pad9)") (class "Default")
      (node (ref "SV5") (pin "9") (pinfunction "9_9") (pintype "passive"))
    )
    (net (code "169") (name "unconnected-(SV5-Pad10)") (class "Default")
      (node (ref "SV5") (pin "10") (pinfunction "10_10") (pintype "passive"))
    )
    (net (code "170") (name "unconnected-(SV5-Pad11)") (class "Default")
      (node (ref "SV5") (pin "11") (pinfunction "11_11") (pintype "passive"))
    )
    (net (code "171") (name "unconnected-(SV5-Pad12)") (class "Default")
      (node (ref "SV5") (pin "12") (pinfunction "12_12") (pintype "passive"))
    )
    (net (code "172") (name "unconnected-(SV5-Pad13)") (class "Default")
      (node (ref "SV5") (pin "13") (pinfunction "13_13") (pintype "passive"))
    )
    (net (code "173") (name "unconnected-(SV5-Pad14)") (class "Default")
      (node (ref "SV5") (pin "14") (pinfunction "14_14") (pintype "passive"))
    )
    (net (code "174") (name "unconnected-(SV5-Pad15)") (class "Default")
      (node (ref "SV5") (pin "15") (pinfunction "15_15") (pintype "passive"))
    )
    (net (code "175") (name "unconnected-(SV5-Pad16)") (class "Default")
      (node (ref "SV5") (pin "16") (pinfunction "16_16") (pintype "passive"))
    )
    (net (code "176") (name "unconnected-(SV5-Pad17)") (class "Default")
      (node (ref "SV5") (pin "17") (pinfunction "17_17") (pintype "passive"))
    )
    (net (code "177") (name "unconnected-(SV5-Pad18)") (class "Default")
      (node (ref "SV5") (pin "18") (pinfunction "18_18") (pintype "passive"))
    )
    (net (code "178") (name "unconnected-(SV5-Pad19)") (class "Default")
      (node (ref "SV5") (pin "19") (pinfunction "19_19") (pintype "passive"))
    )
    (net (code "179") (name "unconnected-(SV5-Pad20)") (class "Default")
      (node (ref "SV5") (pin "20") (pinfunction "20_20") (pintype "passive"))
    )
    (net (code "180") (name "unconnected-(SV5-Pad21)") (class "Default")
      (node (ref "SV5") (pin "21") (pinfunction "21_21") (pintype "passive"))
    )
    (net (code "181") (name "unconnected-(SV5-Pad22)") (class "Default")
      (node (ref "SV5") (pin "22") (pinfunction "22_22") (pintype "passive"))
    )
    (net (code "182") (name "unconnected-(SV5-Pad23)") (class "Default")
      (node (ref "SV5") (pin "23") (pinfunction "23_23") (pintype "passive"))
    )
    (net (code "183") (name "unconnected-(SV5-Pad24)") (class "Default")
      (node (ref "SV5") (pin "24") (pinfunction "24_24") (pintype "passive"))
    )
    (net (code "184") (name "unconnected-(SV5-Pad25)") (class "Default")
      (node (ref "SV5") (pin "25") (pinfunction "25_25") (pintype "passive"))
    )
    (net (code "185") (name "unconnected-(SV5-Pad26)") (class "Default")
      (node (ref "SV5") (pin "26") (pinfunction "26_26") (pintype "passive"))
    )
    (net (code "186") (name "unconnected-(SV5-Pad27)") (class "Default")
      (node (ref "SV5") (pin "27") (pinfunction "27_27") (pintype "passive"))
    )
    (net (code "187") (name "unconnected-(SV5-Pad28)") (class "Default")
      (node (ref "SV5") (pin "28") (pinfunction "28_28") (pintype "passive"))
    )
    (net (code "188") (name "unconnected-(SV6-Pad1)") (class "Default")
      (node (ref "SV6") (pin "1") (pinfunction "1_1") (pintype "passive"))
    )
    (net (code "189") (name "unconnected-(SV6-Pad2)") (class "Default")
      (node (ref "SV6") (pin "2") (pinfunction "2_2") (pintype "passive"))
    )
    (net (code "190") (name "unconnected-(SV6-Pad3)") (class "Default")
      (node (ref "SV6") (pin "3") (pinfunction "3_3") (pintype "passive"))
    )
    (net (code "191") (name "unconnected-(SV6-Pad4)") (class "Default")
      (node (ref "SV6") (pin "4") (pinfunction "4_4") (pintype "passive"))
    )
    (net (code "192") (name "unconnected-(SV6-Pad5)") (class "Default")
      (node (ref "SV6") (pin "5") (pinfunction "5_5") (pintype "passive"))
    )
    (net (code "193") (name "unconnected-(SV6-Pad6)") (class "Default")
      (node (ref "SV6") (pin "6") (pinfunction "6_6") (pintype "passive"))
    )
    (net (code "194") (name "unconnected-(SV6-Pad7)") (class "Default")
      (node (ref "SV6") (pin "7") (pinfunction "7_7") (pintype "passive"))
    )
    (net (code "195") (name "unconnected-(SV6-Pad8)") (class "Default")
      (node (ref "SV6") (pin "8") (pinfunction "8_8") (pintype "passive"))
    )
    (net (code "196") (name "unconnected-(SV6-Pad9)") (class "Default")
      (node (ref "SV6") (pin "9") (pinfunction "9_9") (pintype "passive"))
    )
    (net (code "197") (name "unconnected-(SV6-Pad10)") (class "Default")
      (node (ref "SV6") (pin "10") (pinfunction "10_10") (pintype "passive"))
    )
    (net (code "198") (name "unconnected-(SV6-Pad11)") (class "Default")
      (node (ref "SV6") (pin "11") (pinfunction "11_11") (pintype "passive"))
    )
    (net (code "199") (name "unconnected-(SV6-Pad12)") (class "Default")
      (node (ref "SV6") (pin "12") (pinfunction "12_12") (pintype "passive"))
    )
    (net (code "200") (name "unconnected-(SV6-Pad13)") (class "Default")
      (node (ref "SV6") (pin "13") (pinfunction "13_13") (pintype "passive"))
    )
    (net (code "201") (name "unconnected-(SV6-Pad14)") (class "Default")
      (node (ref "SV6") (pin "14") (pinfunction "14_14") (pintype "passive"))
    )
    (net (code "202") (name "unconnected-(SV6-Pad15)") (class "Default")
      (node (ref "SV6") (pin "15") (pinfunction "15_15") (pintype "passive"))
    )
    (net (code "203") (name "unconnected-(SV6-Pad16)") (class "Default")
      (node (ref "SV6") (pin "16") (pinfunction "16_16") (pintype "passive"))
    )
    (net (code "204") (name "unconnected-(SV6-Pad17)") (class "Default")
      (node (ref "SV6") (pin "17") (pinfunction "17_17") (pintype "passive"))
    )
    (net (code "205") (name "unconnected-(SV6-Pad18)") (class "Default")
      (node (ref "SV6") (pin "18") (pinfunction "18_18") (pintype "passive"))
    )
    (net (code "206") (name "unconnected-(SV6-Pad19)") (class "Default")
      (node (ref "SV6") (pin "19") (pinfunction "19_19") (pintype "passive"))
    )
    (net (code "207") (name "unconnected-(SV6-Pad20)") (class "Default")
      (node (ref "SV6") (pin "20") (pinfunction "20_20") (pintype "passive"))
    )
    (net (code "208") (name "unconnected-(SV6-Pad21)") (class "Default")
      (node (ref "SV6") (pin "21") (pinfunction "21_21") (pintype "passive"))
    )
    (net (code "209") (name "unconnected-(SV6-Pad22)") (class "Default")
      (node (ref "SV6") (pin "22") (pinfunction "22_22") (pintype "passive"))
    )
    (net (code "210") (name "unconnected-(SV6-Pad23)") (class "Default")
      (node (ref "SV6") (pin "23") (pinfunction "23_23") (pintype "passive"))
    )
    (net (code "211") (name "unconnected-(SV6-Pad24)") (class "Default")
      (node (ref "SV6") (pin "24") (pinfunction "24_24") (pintype "passive"))
    )
    (net (code "212") (name "unconnected-(SV6-Pad25)") (class "Default")
      (node (ref "SV6") (pin "25") (pinfunction "25_25") (pintype "passive"))
    )
    (net (code "213") (name "unconnected-(SV6-Pad26)") (class "Default")
      (node (ref "SV6") (pin "26") (pinfunction "26_26") (pintype "passive"))
    )
    (net (code "214") (name "unconnected-(SV6-Pad27)") (class "Default")
      (node (ref "SV6") (pin "27") (pinfunction "27_27") (pintype "passive"))
    )
    (net (code "215") (name "unconnected-(SV6-Pad28)") (class "Default")
      (node (ref "SV6") (pin "28") (pinfunction "28_28") (pintype "passive"))
    )
    (net (code "216") (name "unconnected-(SV7-Pad1)") (class "Default")
      (node (ref "SV7") (pin "1") (pinfunction "1_1") (pintype "passive"))
    )
    (net (code "217") (name "unconnected-(SV7-Pad2)") (class "Default")
      (node (ref "SV7") (pin "2") (pinfunction "2_2") (pintype "passive"))
    )
    (net (code "218") (name "unconnected-(SV7-Pad3)") (class "Default")
      (node (ref "SV7") (pin "3") (pinfunction "3_3") (pintype "passive"))
    )
    (net (code "219") (name "unconnected-(SV7-Pad4)") (class "Default")
      (node (ref "SV7") (pin "4") (pinfunction "4_4") (pintype "passive"))
    )
    (net (code "220") (name "unconnected-(SV7-Pad5)") (class "Default")
      (node (ref "SV7") (pin "5") (pinfunction "5_5") (pintype "passive"))
    )
    (net (code "221") (name "unconnected-(SV7-Pad6)") (class "Default")
      (node (ref "SV7") (pin "6") (pinfunction "6_6") (pintype "passive"))
    )
    (net (code "222") (name "unconnected-(SV7-Pad7)") (class "Default")
      (node (ref "SV7") (pin "7") (pinfunction "7_7") (pintype "passive"))
    )
    (net (code "223") (name "unconnected-(SV7-Pad8)") (class "Default")
      (node (ref "SV7") (pin "8") (pinfunction "8_8") (pintype "passive"))
    )
    (net (code "224") (name "unconnected-(SV7-Pad9)") (class "Default")
      (node (ref "SV7") (pin "9") (pinfunction "9_9") (pintype "passive"))
    )
    (net (code "225") (name "unconnected-(SV7-Pad10)") (class "Default")
      (node (ref "SV7") (pin "10") (pinfunction "10_10") (pintype "passive"))
    )
    (net (code "226") (name "unconnected-(SV7-Pad11)") (class "Default")
      (node (ref "SV7") (pin "11") (pinfunction "11_11") (pintype "passive"))
    )
    (net (code "227") (name "unconnected-(SV7-Pad12)") (class "Default")
      (node (ref "SV7") (pin "12") (pinfunction "12_12") (pintype "passive"))
    )
    (net (code "228") (name "unconnected-(SV7-Pad13)") (class "Default")
      (node (ref "SV7") (pin "13") (pinfunction "13_13") (pintype "passive"))
    )
    (net (code "229") (name "unconnected-(SV7-Pad14)") (class "Default")
      (node (ref "SV7") (pin "14") (pinfunction "14_14") (pintype "passive"))
    )
    (net (code "230") (name "unconnected-(SV7-Pad15)") (class "Default")
      (node (ref "SV7") (pin "15") (pinfunction "15_15") (pintype "passive"))
    )
    (net (code "231") (name "unconnected-(SV7-Pad16)") (class "Default")
      (node (ref "SV7") (pin "16") (pinfunction "16_16") (pintype "passive"))
    )
    (net (code "232") (name "unconnected-(SV7-Pad17)") (class "Default")
      (node (ref "SV7") (pin "17") (pinfunction "17_17") (pintype "passive"))
    )
    (net (code "233") (name "unconnected-(SV7-Pad18)") (class "Default")
      (node (ref "SV7") (pin "18") (pinfunction "18_18") (pintype "passive"))
    )
    (net (code "234") (name "unconnected-(SV7-Pad19)") (class "Default")
      (node (ref "SV7") (pin "19") (pinfunction "19_19") (pintype "passive"))
    )
    (net (code "235") (name "unconnected-(SV7-Pad20)") (class "Default")
      (node (ref "SV7") (pin "20") (pinfunction "20_20") (pintype "passive"))
    )
    (net (code "236") (name "unconnected-(SV7-Pad21)") (class "Default")
      (node (ref "SV7") (pin "21") (pinfunction "21_21") (pintype "passive"))
    )
    (net (code "237") (name "unconnected-(SV7-Pad22)") (class "Default")
      (node (ref "SV7") (pin "22") (pinfunction "22_22") (pintype "passive"))
    )
    (net (code "238") (name "unconnected-(SV7-Pad23)") (class "Default")
      (node (ref "SV7") (pin "23") (pinfunction "23_23") (pintype "passive"))
    )
    (net (code "239") (name "unconnected-(SV7-Pad24)") (class "Default")
      (node (ref "SV7") (pin "24") (pinfunction "24_24") (pintype "passive"))
    )
    (net (code "240") (name "unconnected-(SV7-Pad25)") (class "Default")
      (node (ref "SV7") (pin "25") (pinfunction "25_25") (pintype "passive"))
    )
    (net (code "241") (name "unconnected-(SV7-Pad26)") (class "Default")
      (node (ref "SV7") (pin "26") (pinfunction "26_26") (pintype "passive"))
    )
    (net (code "242") (name "unconnected-(SV7-Pad27)") (class "Default")
      (node (ref "SV7") (pin "27") (pinfunction "27_27") (pintype "passive"))
    )
    (net (code "243") (name "unconnected-(SV7-Pad28)") (class "Default")
      (node (ref "SV7") (pin "28") (pinfunction "28_28") (pintype "passive"))
    )
    (net (code "244") (name "unconnected-(SV8-Pad1)") (class "Default")
      (node (ref "SV8") (pin "1") (pinfunction "1_1") (pintype "passive"))
    )
    (net (code "245") (name "unconnected-(SV8-Pad2)") (class "Default")
      (node (ref "SV8") (pin "2") (pinfunction "2_2") (pintype "passive"))
    )
    (net (code "246") (name "unconnected-(SV8-Pad3)") (class "Default")
      (node (ref "SV8") (pin "3") (pinfunction "3_3") (pintype "passive"))
    )
    (net (code "247") (name "unconnected-(SV8-Pad4)") (class "Default")
      (node (ref "SV8") (pin "4") (pinfunction "4_4") (pintype "passive"))
    )
    (net (code "248") (name "unconnected-(SV8-Pad5)") (class "Default")
      (node (ref "SV8") (pin "5") (pinfunction "5_5") (pintype "passive"))
    )
    (net (code "249") (name "unconnected-(SV8-Pad6)") (class "Default")
      (node (ref "SV8") (pin "6") (pinfunction "6_6") (pintype "passive"))
    )
    (net (code "250") (name "unconnected-(SV8-Pad7)") (class "Default")
      (node (ref "SV8") (pin "7") (pinfunction "7_7") (pintype "passive"))
    )
    (net (code "251") (name "unconnected-(SV8-Pad8)") (class "Default")
      (node (ref "SV8") (pin "8") (pinfunction "8_8") (pintype "passive"))
    )
    (net (code "252") (name "unconnected-(SV8-Pad9)") (class "Default")
      (node (ref "SV8") (pin "9") (pinfunction "9_9") (pintype "passive"))
    )
    (net (code "253") (name "unconnected-(SV8-Pad10)") (class "Default")
      (node (ref "SV8") (pin "10") (pinfunction "10_10") (pintype "passive"))
    )
    (net (code "254") (name "unconnected-(SV8-Pad11)") (class "Default")
      (node (ref "SV8") (pin "11") (pinfunction "11_11") (pintype "passive"))
    )
    (net (code "255") (name "unconnected-(SV8-Pad12)") (class "Default")
      (node (ref "SV8") (pin "12") (pinfunction "12_12") (pintype "passive"))
    )
    (net (code "256") (name "unconnected-(SV8-Pad13)") (class "Default")
      (node (ref "SV8") (pin "13") (pinfunction "13_13") (pintype "passive"))
    )
    (net (code "257") (name "unconnected-(SV8-Pad14)") (class "Default")
      (node (ref "SV8") (pin "14") (pinfunction "14_14") (pintype "passive"))
    )
    (net (code "258") (name "unconnected-(SV8-Pad15)") (class "Default")
      (node (ref "SV8") (pin "15") (pinfunction "15_15") (pintype "passive"))
    )
    (net (code "259") (name "unconnected-(SV8-Pad16)") (class "Default")
      (node (ref "SV8") (pin "16") (pinfunction "16_16") (pintype "passive"))
    )
    (net (code "260") (name "unconnected-(SV8-Pad17)") (class "Default")
      (node (ref "SV8") (pin "17") (pinfunction "17_17") (pintype "passive"))
    )
    (net (code "261") (name "unconnected-(SV8-Pad18)") (class "Default")
      (node (ref "SV8") (pin "18") (pinfunction "18_18") (pintype "passive"))
    )
    (net (code "262") (name "unconnected-(SV8-Pad19)") (class "Default")
      (node (ref "SV8") (pin "19") (pinfunction "19_19") (pintype "passive"))
    )
    (net (code "263") (name "unconnected-(SV8-Pad20)") (class "Default")
      (node (ref "SV8") (pin "20") (pinfunction "20_20") (pintype "passive"))
    )
    (net (code "264") (name "unconnected-(SV8-Pad21)") (class "Default")
      (node (ref "SV8") (pin "21") (pinfunction "21_21") (pintype "passive"))
    )
    (net (code "265") (name "unconnected-(SV8-Pad22)") (class "Default")
      (node (ref "SV8") (pin "22") (pinfunction "22_22") (pintype "passive"))
    )
    (net (code "266") (name "unconnected-(SV8-Pad23)") (class "Default")
      (node (ref "SV8") (pin "23") (pinfunction "23_23") (pintype "passive"))
    )
    (net (code "267") (name "unconnected-(SV8-Pad24)") (class "Default")
      (node (ref "SV8") (pin "24") (pinfunction "24_24") (pintype "passive"))
    )
    (net (code "268") (name "unconnected-(SV8-Pad25)") (class "Default")
      (node (ref "SV8") (pin "25") (pinfunction "25_25") (pintype "passive"))
    )
    (net (code "269") (name "unconnected-(SV8-Pad26)") (class "Default")
      (node (ref "SV8") (pin "26") (pinfunction "26_26") (pintype "passive"))
    )
    (net (code "270") (name "unconnected-(SV8-Pad27)") (class "Default")
      (node (ref "SV8") (pin "27") (pinfunction "27_27") (pintype "passive"))
    )
    (net (code "271") (name "unconnected-(SV8-Pad28)") (class "Default")
      (node (ref "SV8") (pin "28") (pinfunction "28_28") (pintype "passive"))
    )
    (net (code "272") (name "unconnected-(SV9-Pad1)") (class "Default")
      (node (ref "SV9") (pin "1") (pinfunction "1_1") (pintype "passive"))
    )
    (net (code "273") (name "unconnected-(SV9-Pad2)") (class "Default")
      (node (ref "SV9") (pin "2") (pinfunction "2_2") (pintype "passive"))
    )
    (net (code "274") (name "unconnected-(SV9-Pad3)") (class "Default")
      (node (ref "SV9") (pin "3") (pinfunction "3_3") (pintype "passive"))
    )
    (net (code "275") (name "unconnected-(SV9-Pad4)") (class "Default")
      (node (ref "SV9") (pin "4") (pinfunction "4_4") (pintype "passive"))
    )
    (net (code "276") (name "unconnected-(SV9-Pad5)") (class "Default")
      (node (ref "SV9") (pin "5") (pinfunction "5_5") (pintype "passive"))
    )
    (net (code "277") (name "unconnected-(SV9-Pad6)") (class "Default")
      (node (ref "SV9") (pin "6") (pinfunction "6_6") (pintype "passive"))
    )
    (net (code "278") (name "unconnected-(SV9-Pad7)") (class "Default")
      (node (ref "SV9") (pin "7") (pinfunction "7_7") (pintype "passive"))
    )
    (net (code "279") (name "unconnected-(SV9-Pad8)") (class "Default")
      (node (ref "SV9") (pin "8") (pinfunction "8_8") (pintype "passive"))
    )
    (net (code "280") (name "unconnected-(SV9-Pad9)") (class "Default")
      (node (ref "SV9") (pin "9") (pinfunction "9_9") (pintype "passive"))
    )
    (net (code "281") (name "unconnected-(SV9-Pad10)") (class "Default")
      (node (ref "SV9") (pin "10") (pinfunction "10_10") (pintype "passive"))
    )
    (net (code "282") (name "unconnected-(SV9-Pad11)") (class "Default")
      (node (ref "SV9") (pin "11") (pinfunction "11_11") (pintype "passive"))
    )
    (net (code "283") (name "unconnected-(SV9-Pad12)") (class "Default")
      (node (ref "SV9") (pin "12") (pinfunction "12_12") (pintype "passive"))
    )
    (net (code "284") (name "unconnected-(SV9-Pad13)") (class "Default")
      (node (ref "SV9") (pin "13") (pinfunction "13_13") (pintype "passive"))
    )
    (net (code "285") (name "unconnected-(SV9-Pad14)") (class "Default")
      (node (ref "SV9") (pin "14") (pinfunction "14_14") (pintype "passive"))
    )
    (net (code "286") (name "unconnected-(SV9-Pad15)") (class "Default")
      (node (ref "SV9") (pin "15") (pinfunction "15_15") (pintype "passive"))
    )
    (net (code "287") (name "unconnected-(SV9-Pad16)") (class "Default")
      (node (ref "SV9") (pin "16") (pinfunction "16_16") (pintype "passive"))
    )
    (net (code "288") (name "unconnected-(SV9-Pad17)") (class "Default")
      (node (ref "SV9") (pin "17") (pinfunction "17_17") (pintype "passive"))
    )
    (net (code "289") (name "unconnected-(SV9-Pad18)") (class "Default")
      (node (ref "SV9") (pin "18") (pinfunction "18_18") (pintype "passive"))
    )
    (net (code "290") (name "unconnected-(SV9-Pad19)") (class "Default")
      (node (ref "SV9") (pin "19") (pinfunction "19_19") (pintype "passive"))
    )
    (net (code "291") (name "unconnected-(SV9-Pad20)") (class "Default")
      (node (ref "SV9") (pin "20") (pinfunction "20_20") (pintype "passive"))
    )
    (net (code "292") (name "unconnected-(SV9-Pad21)") (class "Default")
      (node (ref "SV9") (pin "21") (pinfunction "21_21") (pintype "passive"))
    )
    (net (code "293") (name "unconnected-(SV9-Pad22)") (class "Default")
      (node (ref "SV9") (pin "22") (pinfunction "22_22") (pintype "passive"))
    )
    (net (code "294") (name "unconnected-(SV9-Pad23)") (class "Default")
      (node (ref "SV9") (pin "23") (pinfunction "23_23") (pintype "passive"))
    )
    (net (code "295") (name "unconnected-(SV9-Pad24)") (class "Default")
      (node (ref "SV9") (pin "24") (pinfunction "24_24") (pintype "passive"))
    )
    (net (code "296") (name "unconnected-(SV9-Pad25)") (class "Default")
      (node (ref "SV9") (pin "25") (pinfunction "25_25") (pintype "passive"))
    )
    (net (code "297") (name "unconnected-(SV9-Pad26)") (class "Default")
      (node (ref "SV9") (pin "26") (pinfunction "26_26") (pintype "passive"))
    )
    (net (code "298") (name "unconnected-(SV9-Pad27)") (class "Default")
      (node (ref "SV9") (pin "27") (pinfunction "27_27") (pintype "passive"))
    )
    (net (code "299") (name "unconnected-(SV9-Pad28)") (class "Default")
      (node (ref "SV9") (pin "28") (pinfunction "28_28") (pintype "passive"))
    )
    (net (code "300") (name "unconnected-(SV10-Pad1)") (class "Default")
      (node (ref "SV10") (pin "1") (pinfunction "1_1") (pintype "passive"))
    )
    (net (code "301") (name "unconnected-(SV10-Pad2)") (class "Default")
      (node (ref "SV10") (pin "2") (pinfunction "2_2") (pintype "passive"))
    )
    (net (code "302") (name "unconnected-(SV10-Pad3)") (class "Default")
      (node (ref "SV10") (pin "3") (pinfunction "3_3") (pintype "passive"))
    )
    (net (code "303") (name "unconnected-(SV10-Pad4)") (class "Default")
      (node (ref "SV10") (pin "4") (pinfunction "4_4") (pintype "passive"))
    )
    (net (code "304") (name "unconnected-(SV10-Pad5)") (class "Default")
      (node (ref "SV10") (pin "5") (pinfunction "5_5") (pintype "passive"))
    )
    (net (code "305") (name "unconnected-(SV10-Pad6)") (class "Default")
      (node (ref "SV10") (pin "6") (pinfunction "6_6") (pintype "passive"))
    )
    (net (code "306") (name "unconnected-(SV10-Pad7)") (class "Default")
      (node (ref "SV10") (pin "7") (pinfunction "7_7") (pintype "passive"))
    )
    (net (code "307") (name "unconnected-(SV10-Pad8)") (class "Default")
      (node (ref "SV10") (pin "8") (pinfunction "8_8") (pintype "passive"))
    )
    (net (code "308") (name "unconnected-(SV10-Pad9)") (class "Default")
      (node (ref "SV10") (pin "9") (pinfunction "9_9") (pintype "passive"))
    )
    (net (code "309") (name "unconnected-(SV10-Pad10)") (class "Default")
      (node (ref "SV10") (pin "10") (pinfunction "10_10") (pintype "passive"))
    )
    (net (code "310") (name "unconnected-(SV10-Pad11)") (class "Default")
      (node (ref "SV10") (pin "11") (pinfunction "11_11") (pintype "passive"))
    )
    (net (code "311") (name "unconnected-(SV10-Pad12)") (class "Default")
      (node (ref "SV10") (pin "12") (pinfunction "12_12") (pintype "passive"))
    )
    (net (code "312") (name "unconnected-(SV10-Pad13)") (class "Default")
      (node (ref "SV10") (pin "13") (pinfunction "13_13") (pintype "passive"))
    )
    (net (code "313") (name "unconnected-(SV10-Pad14)") (class "Default")
      (node (ref "SV10") (pin "14") (pinfunction "14_14") (pintype "passive"))
    )
    (net (code "314") (name "unconnected-(SV10-Pad15)") (class "Default")
      (node (ref "SV10") (pin "15") (pinfunction "15_15") (pintype "passive"))
    )
    (net (code "315") (name "unconnected-(SV10-Pad16)") (class "Default")
      (node (ref "SV10") (pin "16") (pinfunction "16_16") (pintype "passive"))
    )
    (net (code "316") (name "unconnected-(SV10-Pad17)") (class "Default")
      (node (ref "SV10") (pin "17") (pinfunction "17_17") (pintype "passive"))
    )
    (net (code "317") (name "unconnected-(SV10-Pad18)") (class "Default")
      (node (ref "SV10") (pin "18") (pinfunction "18_18") (pintype "passive"))
    )
    (net (code "318") (name "unconnected-(SV10-Pad19)") (class "Default")
      (node (ref "SV10") (pin "19") (pinfunction "19_19") (pintype "passive"))
    )
    (net (code "319") (name "unconnected-(SV10-Pad20)") (class "Default")
      (node (ref "SV10") (pin "20") (pinfunction "20_20") (pintype "passive"))
    )
    (net (code "320") (name "unconnected-(SV10-Pad21)") (class "Default")
      (node (ref "SV10") (pin "21") (pinfunction "21_21") (pintype "passive"))
    )
    (net (code "321") (name "unconnected-(SV10-Pad22)") (class "Default")
      (node (ref "SV10") (pin "22") (pinfunction "22_22") (pintype "passive"))
    )
    (net (code "322") (name "unconnected-(SV10-Pad23)") (class "Default")
      (node (ref "SV10") (pin "23") (pinfunction "23_23") (pintype "passive"))
    )
    (net (code "323") (name "unconnected-(SV10-Pad24)") (class "Default")
      (node (ref "SV10") (pin "24") (pinfunction "24_24") (pintype "passive"))
    )
    (net (code "324") (name "unconnected-(SV10-Pad25)") (class "Default")
      (node (ref "SV10") (pin "25") (pinfunction "25_25") (pintype "passive"))
    )
    (net (code "325") (name "unconnected-(SV10-Pad26)") (class "Default")
      (node (ref "SV10") (pin "26") (pinfunction "26_26") (pintype "passive"))
    )
    (net (code "326") (name "unconnected-(SV10-Pad27)") (class "Default")
      (node (ref "SV10") (pin "27") (pinfunction "27_27") (pintype "passive"))
    )
    (net (code "327") (name "unconnected-(SV10-Pad28)") (class "Default")
      (node (ref "SV10") (pin "28") (pinfunction "28_28") (pintype "passive"))
    )
    (net (code "328") (name "unconnected-(SV11-Pad1)") (class "Default")
      (node (ref "SV11") (pin "1") (pinfunction "1_1") (pintype "passive"))
    )
    (net (code "329") (name "unconnected-(SV11-Pad2)") (class "Default")
      (node (ref "SV11") (pin "2") (pinfunction "2_2") (pintype "passive"))
    )
    (net (code "330") (name "unconnected-(SV11-Pad3)") (class "Default")
      (node (ref "SV11") (pin "3") (pinfunction "3_3") (pintype "passive"))
    )
    (net (code "331") (name "unconnected-(SV11-Pad4)") (class "Default")
      (node (ref "SV11") (pin "4") (pinfunction "4_4") (pintype "passive"))
    )
    (net (code "332") (name "unconnected-(SV11-Pad5)") (class "Default")
      (node (ref "SV11") (pin "5") (pinfunction "5_5") (pintype "passive"))
    )
    (net (code "333") (name "unconnected-(SV11-Pad6)") (class "Default")
      (node (ref "SV11") (pin "6") (pinfunction "6_6") (pintype "passive"))
    )
    (net (code "334") (name "unconnected-(SV11-Pad7)") (class "Default")
      (node (ref "SV11") (pin "7") (pinfunction "7_7") (pintype "passive"))
    )
    (net (code "335") (name "unconnected-(SV11-Pad8)") (class "Default")
      (node (ref "SV11") (pin "8") (pinfunction "8_8") (pintype "passive"))
    )
    (net (code "336") (name "unconnected-(SV11-Pad9)") (class "Default")
      (node (ref "SV11") (pin "9") (pinfunction "9_9") (pintype "passive"))
    )
    (net (code "337") (name "unconnected-(SV11-Pad10)") (class "Default")
      (node (ref "SV11") (pin "10") (pinfunction "10_10") (pintype "passive"))
    )
    (net (code "338") (name "unconnected-(SV11-Pad11)") (class "Default")
      (node (ref "SV11") (pin "11") (pinfunction "11_11") (pintype "passive"))
    )
    (net (code "339") (name "unconnected-(SV11-Pad12)") (class "Default")
      (node (ref "SV11") (pin "12") (pinfunction "12_12") (pintype "passive"))
    )
    (net (code "340") (name "unconnected-(SV11-Pad13)") (class "Default")
      (node (ref "SV11") (pin "13") (pinfunction "13_13") (pintype "passive"))
    )
    (net (code "341") (name "unconnected-(SV11-Pad14)") (class "Default")
      (node (ref "SV11") (pin "14") (pinfunction "14_14") (pintype "passive"))
    )
    (net (code "342") (name "unconnected-(SV11-Pad15)") (class "Default")
      (node (ref "SV11") (pin "15") (pinfunction "15_15") (pintype "passive"))
    )
    (net (code "343") (name "unconnected-(SV11-Pad16)") (class "Default")
      (node (ref "SV11") (pin "16") (pinfunction "16_16") (pintype "passive"))
    )
    (net (code "344") (name "unconnected-(SV11-Pad17)") (class "Default")
      (node (ref "SV11") (pin "17") (pinfunction "17_17") (pintype "passive"))
    )
    (net (code "345") (name "unconnected-(SV11-Pad18)") (class "Default")
      (node (ref "SV11") (pin "18") (pinfunction "18_18") (pintype "passive"))
    )
    (net (code "346") (name "unconnected-(SV11-Pad19)") (class "Default")
      (node (ref "SV11") (pin "19") (pinfunction "19_19") (pintype "passive"))
    )
    (net (code "347") (name "unconnected-(SV11-Pad20)") (class "Default")
      (node (ref "SV11") (pin "20") (pinfunction "20_20") (pintype "passive"))
    )
    (net (code "348") (name "unconnected-(SV11-Pad21)") (class "Default")
      (node (ref "SV11") (pin "21") (pinfunction "21_21") (pintype "passive"))
    )
    (net (code "349") (name "unconnected-(SV11-Pad22)") (class "Default")
      (node (ref "SV11") (pin "22") (pinfunction "22_22") (pintype "passive"))
    )
    (net (code "350") (name "unconnected-(SV11-Pad23)") (class "Default")
      (node (ref "SV11") (pin "23") (pinfunction "23_23") (pintype "passive"))
    )
    (net (code "351") (name "unconnected-(SV11-Pad24)") (class "Default")
      (node (ref "SV11") (pin "24") (pinfunction "24_24") (pintype "passive"))
    )
    (net (code "352") (name "unconnected-(SV11-Pad25)") (class "Default")
      (node (ref "SV11") (pin "25") (pinfunction "25_25") (pintype "passive"))
    )
    (net (code "353") (name "unconnected-(SV11-Pad26)") (class "Default")
      (node (ref "SV11") (pin "26") (pinfunction "26_26") (pintype "passive"))
    )
    (net (code "354") (name "unconnected-(SV11-Pad27)") (class "Default")
      (node (ref "SV11") (pin "27") (pinfunction "27_27") (pintype "passive"))
    )
    (net (code "355") (name "unconnected-(SV11-Pad28)") (class "Default")
      (node (ref "SV11") (pin "28") (pinfunction "28_28") (pintype "passive"))
    )
    (net (code "356") (name "unconnected-(SV12-Pad1)") (class "Default")
      (node (ref "SV12") (pin "1") (pinfunction "1_1") (pintype "passive"))
    )
    (net (code "357") (name "unconnected-(SV12-Pad2)") (class "Default")
      (node (ref "SV12") (pin "2") (pinfunction "2_2") (pintype "passive"))
    )
    (net (code "358") (name "unconnected-(SV12-Pad3)") (class "Default")
      (node (ref "SV12") (pin "3") (pinfunction "3_3") (pintype "passive"))
    )
    (net (code "359") (name "unconnected-(SV12-Pad4)") (class "Default")
      (node (ref "SV12") (pin "4") (pinfunction "4_4") (pintype "passive"))
    )
    (net (code "360") (name "unconnected-(SV12-Pad5)") (class "Default")
      (node (ref "SV12") (pin "5") (pinfunction "5_5") (pintype "passive"))
    )
    (net (code "361") (name "unconnected-(SV12-Pad6)") (class "Default")
      (node (ref "SV12") (pin "6") (pinfunction "6_6") (pintype "passive"))
    )
    (net (code "362") (name "unconnected-(SV12-Pad7)") (class "Default")
      (node (ref "SV12") (pin "7") (pinfunction "7_7") (pintype "passive"))
    )
    (net (code "363") (name "unconnected-(SV12-Pad8)") (class "Default")
      (node (ref "SV12") (pin "8") (pinfunction "8_8") (pintype "passive"))
    )
    (net (code "364") (name "unconnected-(SV12-Pad9)") (class "Default")
      (node (ref "SV12") (pin "9") (pinfunction "9_9") (pintype "passive"))
    )
    (net (code "365") (name "unconnected-(SV12-Pad10)") (class "Default")
      (node (ref "SV12") (pin "10") (pinfunction "10_10") (pintype "passive"))
    )
    (net (code "366") (name "unconnected-(SV12-Pad11)") (class "Default")
      (node (ref "SV12") (pin "11") (pinfunction "11_11") (pintype "passive"))
    )
    (net (code "367") (name "unconnected-(SV12-Pad12)") (class "Default")
      (node (ref "SV12") (pin "12") (pinfunction "12_12") (pintype "passive"))
    )
    (net (code "368") (name "unconnected-(SV12-Pad13)") (class "Default")
      (node (ref "SV12") (pin "13") (pinfunction "13_13") (pintype "passive"))
    )
    (net (code "369") (name "unconnected-(SV12-Pad14)") (class "Default")
      (node (ref "SV12") (pin "14") (pinfunction "14_14") (pintype "passive"))
    )
    (net (code "370") (name "unconnected-(SV12-Pad15)") (class "Default")
      (node (ref "SV12") (pin "15") (pinfunction "15_15") (pintype "passive"))
    )
    (net (code "371") (name "unconnected-(SV12-Pad16)") (class "Default")
      (node (ref "SV12") (pin "16") (pinfunction "16_16") (pintype "passive"))
    )
    (net (code "372") (name "unconnected-(SV12-Pad17)") (class "Default")
      (node (ref "SV12") (pin "17") (pinfunction "17_17") (pintype "passive"))
    )
    (net (code "373") (name "unconnected-(SV12-Pad18)") (class "Default")
      (node (ref "SV12") (pin "18") (pinfunction "18_18") (pintype "passive"))
    )
    (net (code "374") (name "unconnected-(SV12-Pad19)") (class "Default")
      (node (ref "SV12") (pin "19") (pinfunction "19_19") (pintype "passive"))
    )
    (net (code "375") (name "unconnected-(SV12-Pad20)") (class "Default")
      (node (ref "SV12") (pin "20") (pinfunction "20_20") (pintype "passive"))
    )
    (net (code "376") (name "unconnected-(SV12-Pad21)") (class "Default")
      (node (ref "SV12") (pin "21") (pinfunction "21_21") (pintype "passive"))
    )
    (net (code "377") (name "unconnected-(SV12-Pad22)") (class "Default")
      (node (ref "SV12") (pin "22") (pinfunction "22_22") (pintype "passive"))
    )
    (net (code "378") (name "unconnected-(SV12-Pad23)") (class "Default")
      (node (ref "SV12") (pin "23") (pinfunction "23_23") (pintype "passive"))
    )
    (net (code "379") (name "unconnected-(SV12-Pad24)") (class "Default")
      (node (ref "SV12") (pin "24") (pinfunction "24_24") (pintype "passive"))
    )
    (net (code "380") (name "unconnected-(SV12-Pad25)") (class "Default")
      (node (ref "SV12") (pin "25") (pinfunction "25_25") (pintype "passive"))
    )
    (net (code "381") (name "unconnected-(SV12-Pad26)") (class "Default")
      (node (ref "SV12") (pin "26") (pinfunction "26_26") (pintype "passive"))
    )
    (net (code "382") (name "unconnected-(SV12-Pad27)") (class "Default")
      (node (ref "SV12") (pin "27") (pinfunction "27_27") (pintype "passive"))
    )
    (net (code "383") (name "unconnected-(SV12-Pad28)") (class "Default")
      (node (ref "SV12") (pin "28") (pinfunction "28_28") (pintype "passive"))
    )
  )
)
